# DEC3.net
KiCad netlist of a schematic drawn in EAGLE
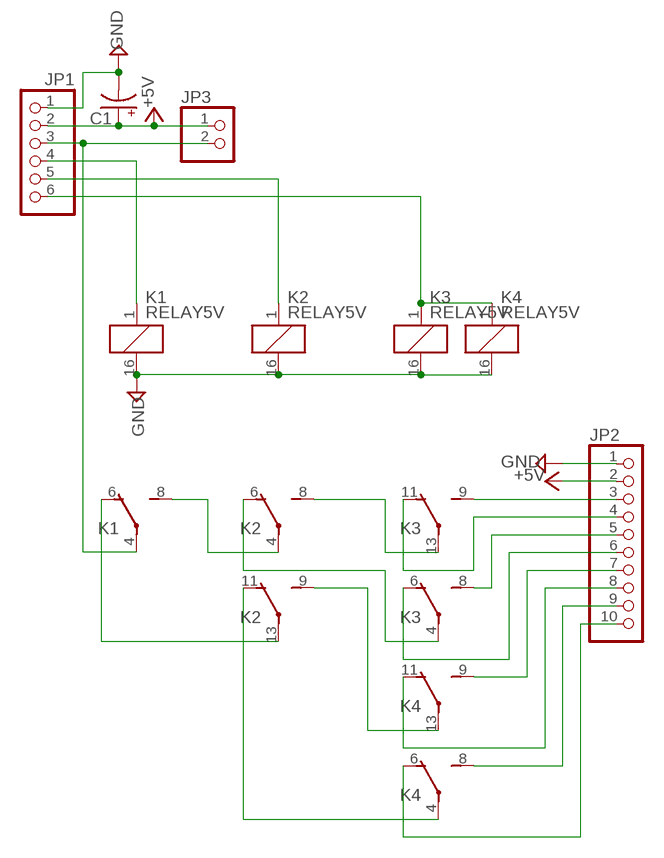
[diagram p0: schematic, sheet 1]

(export (version "E")
  (design (tool "Eeschema 10.0.6"))
  (components
    (comp (ref "C1")
      (value "CC-5-8.5")
      (footprint "eagle-import:E5-8,5")
      (libsource (lib "eagle-import") (part "CC-5-8.5"))
    )
    (comp (ref "JP1")
      (value "PINHD-1X6")
      (footprint "eagle-import:1X06")
      (libsource (lib "eagle-import") (part "PINHD-1X6"))
    )
    (comp (ref "JP2")
      (value "PINHD-1X10")
      (footprint "eagle-import:1X10")
      (libsource (lib "eagle-import") (part "PINHD-1X10"))
    )
    (comp (ref "JP3")
      (value "PINHD-1X2")
      (footprint "eagle-import:1X02")
      (libsource (lib "eagle-import") (part "PINHD-1X2"))
    )
    (comp (ref "K1")
      (value "RELAY5V")
      (footprint "eagle-import:DS-BT")
      (libsource (lib "eagle-import") (part "RELAY5V"))
    )
    (comp (ref "K2")
      (value "RELAY5V")
      (footprint "eagle-import:DS-BT")
      (libsource (lib "eagle-import") (part "RELAY5V"))
    )
    (comp (ref "K3")
      (value "RELAY5V")
      (footprint "eagle-import:DS-BT")
      (libsource (lib "eagle-import") (part "RELAY5V"))
    )
    (comp (ref "K4")
      (value "RELAY5V")
      (footprint "eagle-import:DS-BT")
      (libsource (lib "eagle-import") (part "RELAY5V"))
    )
  )
  (nets
    (net (code "1") (name "+5V") (class "Default")
      (node (ref "C1") (pin "+") (pinfunction "+_+") (pintype "passive"))
      (node (ref "JP1") (pin "2") (pinfunction "2_2") (pintype "passive"))
      (node (ref "JP2") (pin "2") (pinfunction "2_2") (pintype "passive"))
      (node (ref "JP3") (pin "1") (pinfunction "1_1") (pintype "passive"))
    )
    (net (code "2") (name "GND") (class "Default")
      (node (ref "C1") (pin "-") (pinfunction "-_-") (pintype "passive"))
      (node (ref "JP1") (pin "1") (pinfunction "1_1") (pintype "passive"))
      (node (ref "JP2") (pin "1") (pinfunction "1_1") (pintype "passive"))
      (node (ref "K1") (pin "16") (pinfunction "-_16") (pintype "passive"))
      (node (ref "K2") (pin "16") (pinfunction "-_16") (pintype "passive"))
      (node (ref "K3") (pin "16") (pinfunction "-_16") (pintype "passive"))
      (node (ref "K4") (pin "16") (pinfunction "-_16") (pintype "passive"))
    )
    (net (code "3") (name "Net-(K1A-+)") (class "Default")
      (node (ref "JP1") (pin "4") (pinfunction "4_4") (pintype "passive"))
      (node (ref "K1") (pin "1") (pinfunction "+_1") (pintype "passive"))
    )
    (net (code "4") (name "Net-(K1B-O)") (class "Default")
      (node (ref "K1") (pin "6") (pinfunction "O_6") (pintype "passive"))
      (node (ref "K2") (pin "13") (pinfunction "P_13") (pintype "passive"))
    )
    (net (code "5") (name "Net-(K1B-P)") (class "Default")
      (node (ref "JP1") (pin "3") (pinfunction "3_3") (pintype "passive"))
      (node (ref "JP3") (pin "2") (pinfunction "2_2") (pintype "passive"))
      (node (ref "K1") (pin "4") (pinfunction "P_4") (pintype "passive"))
    )
    (net (code "6") (name "Net-(K1B-S)") (class "Default")
      (node (ref "K1") (pin "8") (pinfunction "S_8") (pintype "passive"))
      (node (ref "K2") (pin "4") (pinfunction "P_4") (pintype "passive"))
    )
    (net (code "7") (name "Net-(K2A-+)") (class "Default")
      (node (ref "JP1") (pin "5") (pinfunction "5_5") (pintype "passive"))
      (node (ref "K2") (pin "1") (pinfunction "+_1") (pintype "passive"))
    )
    (net (code "8") (name "Net-(K2B-O)") (class "Default")
      (node (ref "K2") (pin "6") (pinfunction "O_6") (pintype "passive"))
      (node (ref "K3") (pin "4") (pinfunction "P_4") (pintype "passive"))
    )
    (net (code "9") (name "Net-(K2B-S)") (class "Default")
      (node (ref "K2") (pin "8") (pinfunction "S_8") (pintype "passive"))
      (node (ref "K3") (pin "13") (pinfunction "P_13") (pintype "passive"))
    )
    (net (code "10") (name "Net-(K2C-O)") (class "Default")
      (node (ref "K2") (pin "11") (pinfunction "O_11") (pintype "passive"))
      (node (ref "K4") (pin "4") (pinfunction "P_4") (pintype "passive"))
    )
    (net (code "11") (name "Net-(K2C-S)") (class "Default")
      (node (ref "K2") (pin "9") (pinfunction "S_9") (pintype "passive"))
      (node (ref "K4") (pin "13") (pinfunction "P_13") (pintype "passive"))
    )
    (net (code "12") (name "Net-(K3A-+)") (class "Default")
      (node (ref "JP1") (pin "6") (pinfunction "6_6") (pintype "passive"))
      (node (ref "K3") (pin "1") (pinfunction "+_1") (pintype "passive"))
      (node (ref "K4") (pin "1") (pinfunction "+_1") (pintype "passive"))
    )
    (net (code "13") (name "Net-(K3B-O)") (class "Default")
      (node (ref "JP2") (pin "6") (pinfunction "6_6") (pintype "passive"))
      (node (ref "K3") (pin "6") (pinfunction "O_6") (pintype "passive"))
    )
    (net (code "14") (name "Net-(K3B-S)") (class "Default")
      (node (ref "JP2") (pin "5") (pinfunction "5_5") (pintype "passive"))
      (node (ref "K3") (pin "8") (pinfunction "S_8") (pintype "passive"))
    )
    (net (code "15") (name "Net-(K3C-O)") (class "Default")
      (node (ref "JP2") (pin "4") (pinfunction "4_4") (pintype "passive"))
      (node (ref "K3") (pin "11") (pinfunction "O_11") (pintype "passive"))
    )
    (net (code "16") (name "Net-(K3C-S)") (class "Default")
      (node (ref "JP2") (pin "3") (pinfunction "3_3") (pintype "passive"))
      (node (ref "K3") (pin "9") (pinfunction "S_9") (pintype "passive"))
    )
    (net (code "17") (name "Net-(K4B-O)") (class "Default")
      (node (ref "JP2") (pin "10") (pinfunction "10_10") (pintype "passive"))
      (node (ref "K4") (pin "6") (pinfunction "O_6") (pintype "passive"))
    )
    (net (code "18") (name "Net-(K4B-S)") (class "Default")
      (node (ref "JP2") (pin "9") (pinfunction "9_9") (pintype "passive"))
      (node (ref "K4") (pin "8") (pinfunction "S_8") (pintype "passive"))
    )
    (net (code "19") (name "Net-(K4C-O)") (class "Default")
      (node (ref "JP2") (pin "8") (pinfunction "8_8") (pintype "passive"))
      (node (ref "K4") (pin "11") (pinfunction "O_11") (pintype "passive"))
    )
    (net (code "20") (name "Net-(K4C-S)") (class "Default")
      (node (ref "JP2") (pin "7") (pinfunction "7_7") (pintype "passive"))
      (node (ref "K4") (pin "9") (pinfunction "S_9") (pintype "passive"))
    )
  )
)
